# beagle2can.net
KiCad netlist of a schematic drawn in EAGLE
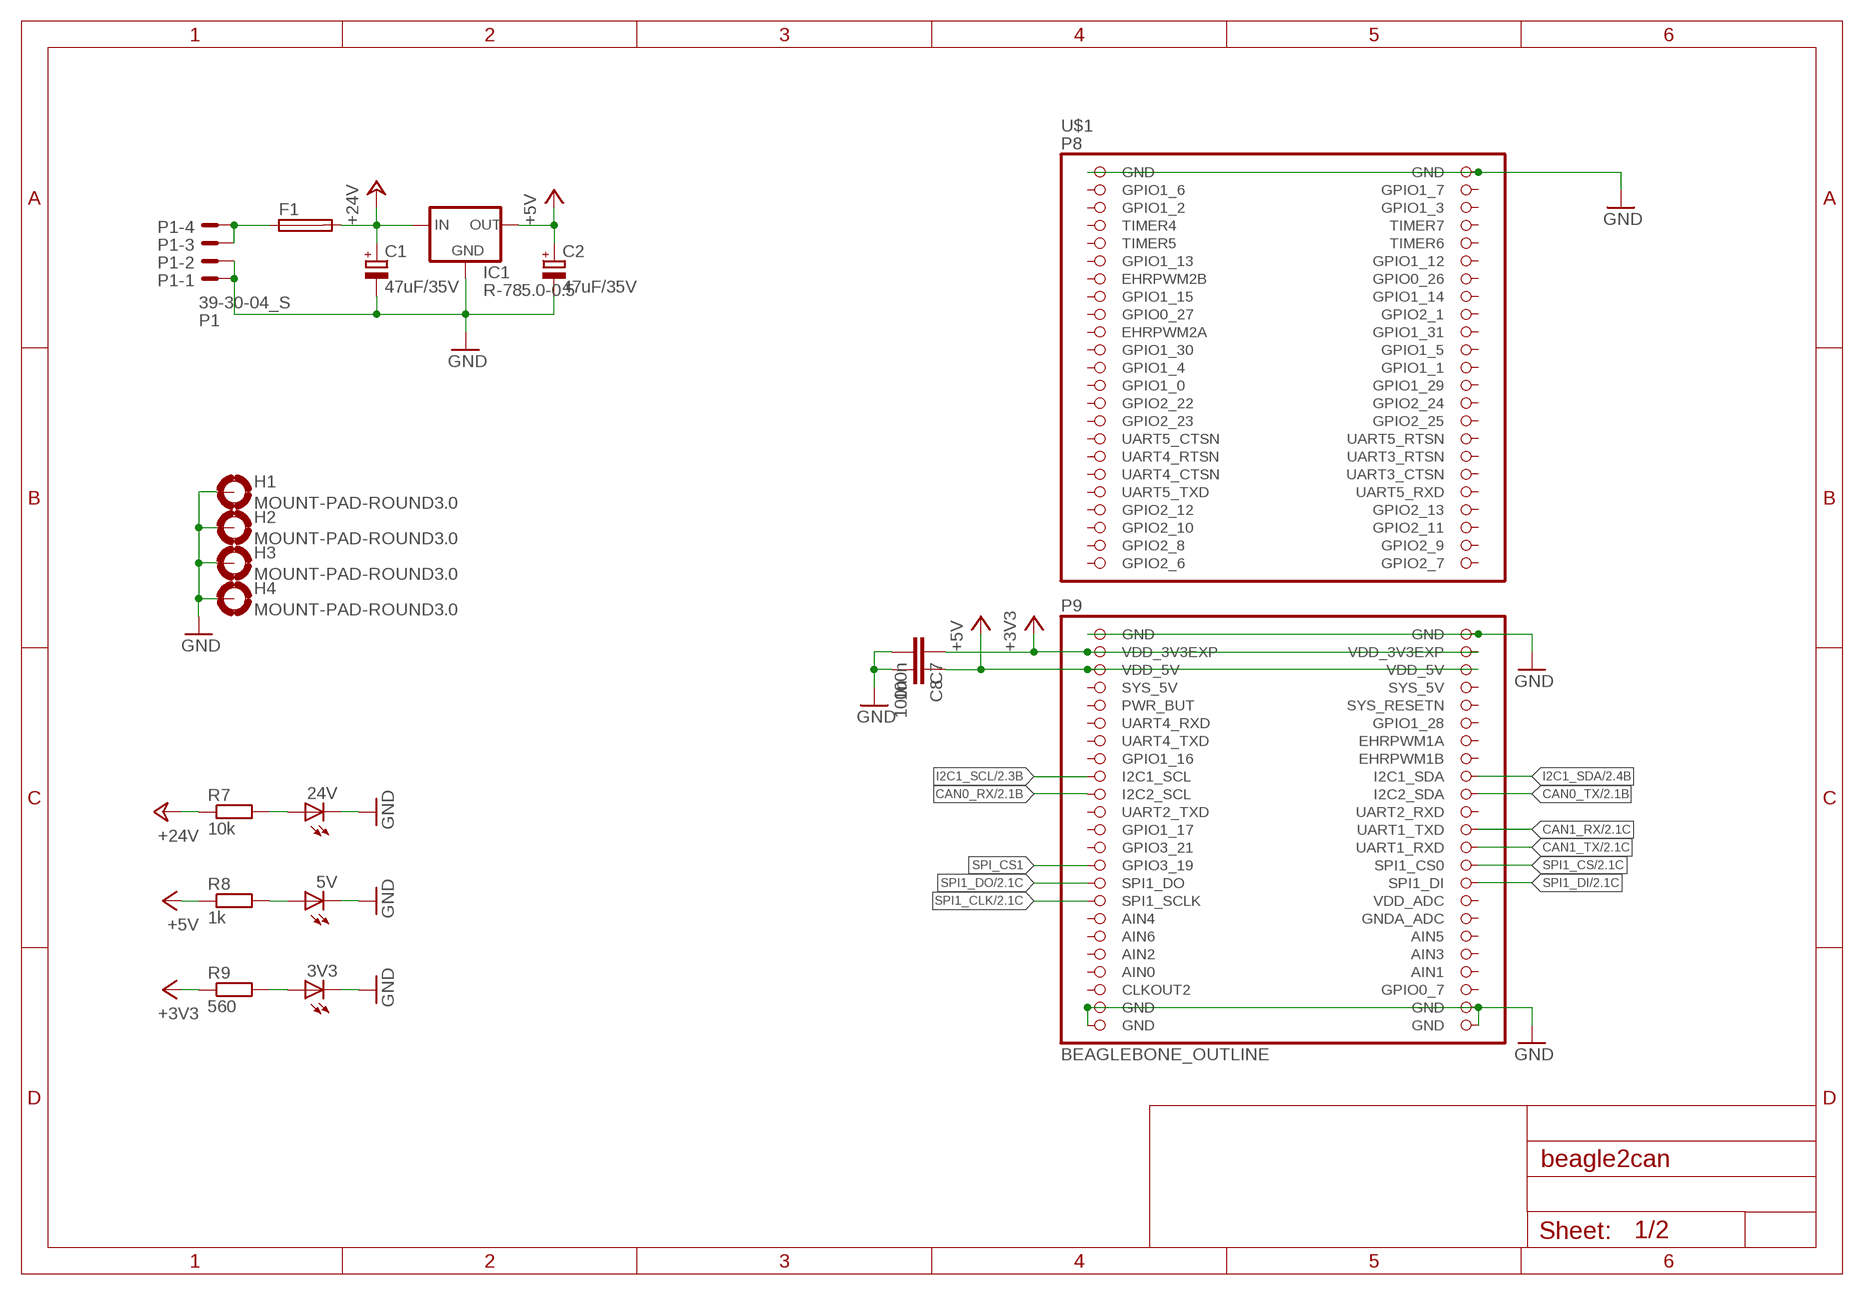
[diagram p0: schematic, sheet 1]
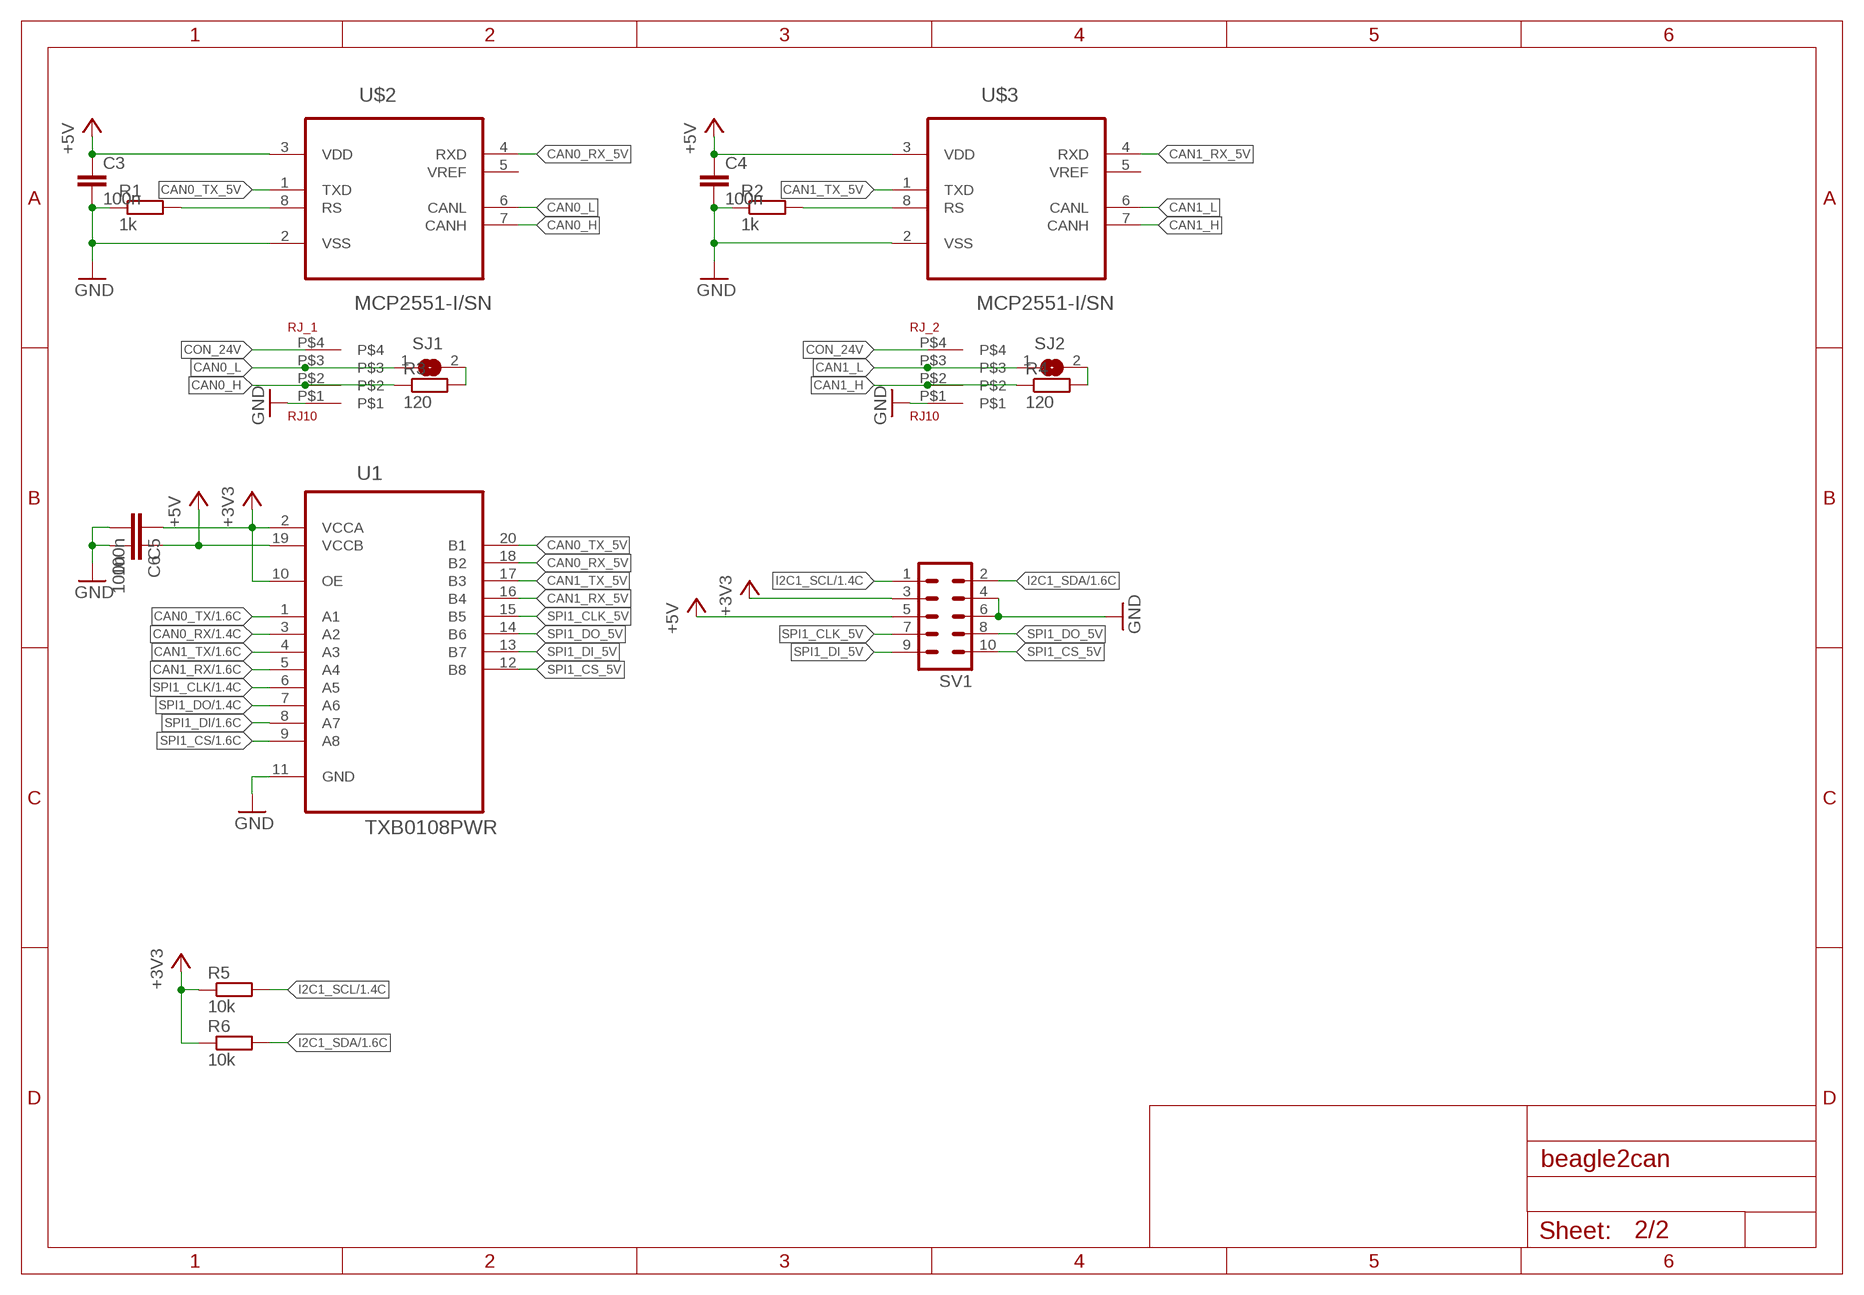
[diagram p1: schematic, sheet 2]

(export (version "E")
  (design (tool "Eeschema 10.0.6"))
  (components
    (comp (ref "3V3")
      (value "LEDCHIP-LED0805")
      (footprint "eagle-import:CHIP-LED0805")
      (libsource (lib "eagle-import") (part "LEDCHIP-LED0805"))
    )
    (comp (ref "5V")
      (value "LEDCHIP-LED0805")
      (footprint "eagle-import:CHIP-LED0805")
      (libsource (lib "eagle-import") (part "LEDCHIP-LED0805"))
    )
    (comp (ref "24V")
      (value "LEDCHIP-LED0805")
      (footprint "eagle-import:CHIP-LED0805")
      (libsource (lib "eagle-import") (part "LEDCHIP-LED0805"))
    )
    (comp (ref "C1")
      (value "47uF/35V")
      (footprint "eagle-import:PANASONIC_D")
      (libsource (lib "eagle-import") (part "CPOL-EUD"))
    )
    (comp (ref "C2")
      (value "47uF/35V")
      (footprint "eagle-import:PANASONIC_D")
      (libsource (lib "eagle-import") (part "CPOL-EUD"))
    )
    (comp (ref "C7")
      (value "100n")
      (footprint "eagle-import:C0603")
      (libsource (lib "eagle-import") (part "C-EUC0603"))
    )
    (comp (ref "C8")
      (value "100n")
      (footprint "eagle-import:C0603")
      (libsource (lib "eagle-import") (part "C-EUC0603"))
    )
    (comp (ref "F1")
      (value "TE5")
      (footprint "eagle-import:TE5")
      (libsource (lib "eagle-import") (part "TE5"))
    )
    (comp (ref "H1")
      (value "MOUNT-PAD-ROUND3.0")
      (footprint "eagle-import:3,0-PAD")
      (libsource (lib "eagle-import") (part "MOUNT-PAD-ROUND3.0"))
    )
    (comp (ref "H2")
      (value "MOUNT-PAD-ROUND3.0")
      (footprint "eagle-import:3,0-PAD")
      (libsource (lib "eagle-import") (part "MOUNT-PAD-ROUND3.0"))
    )
    (comp (ref "H3")
      (value "MOUNT-PAD-ROUND3.0")
      (footprint "eagle-import:3,0-PAD")
      (libsource (lib "eagle-import") (part "MOUNT-PAD-ROUND3.0"))
    )
    (comp (ref "H4")
      (value "MOUNT-PAD-ROUND3.0")
      (footprint "eagle-import:3,0-PAD")
      (libsource (lib "eagle-import") (part "MOUNT-PAD-ROUND3.0"))
    )
    (comp (ref "IC1")
      (value "R-785.0-0.5")
      (footprint "eagle-import:SIP3")
      (fields (field (name "MF") "Recom") (field (name "MPN") "R-785.0-05"))
      (libsource (lib "eagle-import") (part "R-78-0.55.0"))
    )
    (comp (ref "P1")
      (value "39-30-04_S")
      (footprint "eagle-import:39-30-_04_")
      (libsource (lib "eagle-import") (part "39-30-?04?_S"))
    )
    (comp (ref "R7")
      (value "10k")
      (footprint "eagle-import:R0805")
      (libsource (lib "eagle-import") (part "R-EU_R0805"))
    )
    (comp (ref "R8")
      (value "1k")
      (footprint "eagle-import:R0805")
      (libsource (lib "eagle-import") (part "R-EU_R0805"))
    )
    (comp (ref "R9")
      (value "560")
      (footprint "eagle-import:R0805")
      (libsource (lib "eagle-import") (part "R-EU_R0805"))
    )
    (comp (ref "U$1")
      (value "BEAGLEBONE_OUTLINE")
      (footprint "eagle-import:BEAGLEBONE_SHIELD")
      (libsource (lib "eagle-import") (part "BEAGLEBONE_OUTLINE"))
    )
    (comp (ref "C3")
      (value "100n")
      (footprint "eagle-import:C0603")
      (libsource (lib "eagle-import") (part "C-EUC0603"))
    )
    (comp (ref "C4")
      (value "100n")
      (footprint "eagle-import:C0603")
      (libsource (lib "eagle-import") (part "C-EUC0603"))
    )
    (comp (ref "C5")
      (value "100n")
      (footprint "eagle-import:C0603")
      (libsource (lib "eagle-import") (part "C-EUC0603"))
    )
    (comp (ref "C6")
      (value "100n")
      (footprint "eagle-import:C0603")
      (libsource (lib "eagle-import") (part "C-EUC0603"))
    )
    (comp (ref "R1")
      (value "1k")
      (footprint "eagle-import:R0805")
      (libsource (lib "eagle-import") (part "R-EU_R0805"))
    )
    (comp (ref "R2")
      (value "1k")
      (footprint "eagle-import:R0805")
      (libsource (lib "eagle-import") (part "R-EU_R0805"))
    )
    (comp (ref "R3")
      (value "120")
      (footprint "eagle-import:R0805")
      (libsource (lib "eagle-import") (part "R-EU_R0805"))
    )
    (comp (ref "R4")
      (value "120")
      (footprint "eagle-import:R0805")
      (libsource (lib "eagle-import") (part "R-EU_R0805"))
    )
    (comp (ref "R5")
      (value "10k")
      (footprint "eagle-import:R0805")
      (libsource (lib "eagle-import") (part "R-EU_R0805"))
    )
    (comp (ref "R6")
      (value "10k")
      (footprint "eagle-import:R0805")
      (libsource (lib "eagle-import") (part "R-EU_R0805"))
    )
    (comp (ref "RJ_1")
      (value "RJ10")
      (footprint "eagle-import:RJ10")
      (libsource (lib "eagle-import") (part "RJ10"))
    )
    (comp (ref "RJ_2")
      (value "RJ10")
      (footprint "eagle-import:RJ10")
      (libsource (lib "eagle-import") (part "RJ10"))
    )
    (comp (ref "SJ1") (value "SJ") (footprint "eagle-import:SJ") (libsource (lib "eagle-import") (part "SJ")))
    (comp (ref "SJ2") (value "SJ") (footprint "eagle-import:SJ") (libsource (lib "eagle-import") (part "SJ")))
    (comp (ref "SV1")
      (value "ML10L")
      (footprint "eagle-import:ML10L")
      (libsource (lib "eagle-import") (part "ML10L"))
    )
    (comp (ref "U$2")
      (value "MCP2551-I/SN")
      (footprint "eagle-import:SOIC127P600X175-8N")
      (libsource (lib "eagle-import") (part "MCP2551-I/SN"))
    )
    (comp (ref "U$3")
      (value "MCP2551-I/SN")
      (footprint "eagle-import:SOIC127P600X175-8N")
      (libsource (lib "eagle-import") (part "MCP2551-I/SN"))
    )
    (comp (ref "U1")
      (value "TXB0108PWR")
      (footprint "eagle-import:SOP65P640X120-20N")
      (libsource (lib "eagle-import") (part "TXB0108PWR"))
    )
  )
  (nets
    (net (code "1") (name "+3V3") (class "Default")
      (node (ref "C5") (pin "1") (pinfunction "1_1") (pintype "passive"))
      (node (ref "C7") (pin "1") (pinfunction "1_1") (pintype "passive"))
      (node (ref "R5") (pin "1") (pinfunction "1_1") (pintype "passive"))
      (node (ref "R6") (pin "1") (pinfunction "1_1") (pintype "passive"))
      (node (ref "R9") (pin "1") (pinfunction "1_1") (pintype "passive"))
      (node (ref "SV1") (pin "3") (pinfunction "3_3") (pintype "passive"))
      (node (ref "U$1") (pin "49") (pinfunction "VDD_3V3EXP_49") (pintype "power_in"))
      (node (ref "U$1") (pin "50") (pinfunction "VDD_3V3EXP_50") (pintype "power_in"))
      (node (ref "U1") (pin "10") (pinfunction "OE_10") (pintype "input"))
      (node (ref "U1") (pin "2") (pinfunction "VCCA_2") (pintype "power_in"))
    )
    (net (code "2") (name "+5V") (class "Default")
      (node (ref "C2") (pin "+") (pinfunction "+_+") (pintype "passive"))
      (node (ref "C3") (pin "1") (pinfunction "1_1") (pintype "passive"))
      (node (ref "C4") (pin "1") (pinfunction "1_1") (pintype "passive"))
      (node (ref "C6") (pin "1") (pinfunction "1_1") (pintype "passive"))
      (node (ref "C8") (pin "1") (pinfunction "1_1") (pintype "passive"))
      (node (ref "IC1") (pin "3") (pinfunction "OUT_3") (pintype "passive"))
      (node (ref "R8") (pin "1") (pinfunction "1_1") (pintype "passive"))
      (node (ref "SV1") (pin "5") (pinfunction "5_5") (pintype "passive"))
      (node (ref "U$1") (pin "51") (pinfunction "VDD_5V_51") (pintype "power_in"))
      (node (ref "U$1") (pin "52") (pinfunction "VDD_5V_52") (pintype "power_in"))
      (node (ref "U$2") (pin "3") (pinfunction "VDD_3") (pintype "power_in"))
      (node (ref "U$3") (pin "3") (pinfunction "VDD_3") (pintype "power_in"))
      (node (ref "U1") (pin "19") (pinfunction "VCCB_19") (pintype "power_in"))
    )
    (net (code "3") (name "+24V") (class "Default")
      (node (ref "C1") (pin "+") (pinfunction "+_+") (pintype "passive"))
      (node (ref "F1") (pin "2") (pinfunction "2_2") (pintype "passive"))
      (node (ref "IC1") (pin "1") (pinfunction "IN_1") (pintype "input"))
      (node (ref "R7") (pin "1") (pinfunction "1_1") (pintype "passive"))
    )
    (net (code "4") (name "AIN0") (class "Default")
      (node (ref "U$1") (pin "85") (pinfunction "AIN0_85") (pintype "power_in"))
    )
    (net (code "5") (name "CAN0_H") (class "Default")
      (node (ref "R3") (pin "1") (pinfunction "1_1") (pintype "passive"))
      (node (ref "RJ_1") (pin "P$2") (pinfunction "P$2_P$2") (pintype "bidirectional"))
      (node (ref "U$2") (pin "7") (pinfunction "CANH_7") (pintype "bidirectional"))
    )
    (net (code "6") (name "CAN0_L") (class "Default")
      (node (ref "RJ_1") (pin "P$3") (pinfunction "P$3_P$3") (pintype "bidirectional"))
      (node (ref "SJ1") (pin "1") (pinfunction "1_1") (pintype "passive"))
      (node (ref "U$2") (pin "6") (pinfunction "CANL_6") (pintype "bidirectional"))
    )
    (net (code "7") (name "CAN0_RX") (class "Default")
      (node (ref "U$1") (pin "65") (pinfunction "I2C2_SCL_65") (pintype "passive"))
      (node (ref "U1") (pin "3") (pinfunction "A2_3") (pintype "bidirectional"))
    )
    (net (code "8") (name "CAN0_RX_5V") (class "Default")
      (node (ref "U$2") (pin "4") (pinfunction "RXD_4") (pintype "output"))
      (node (ref "U1") (pin "18") (pinfunction "B2_18") (pintype "bidirectional"))
    )
    (net (code "9") (name "CAN0_TX") (class "Default")
      (node (ref "U$1") (pin "66") (pinfunction "I2C2_SDA_66") (pintype "passive"))
      (node (ref "U1") (pin "1") (pinfunction "A1_1") (pintype "bidirectional"))
    )
    (net (code "10") (name "CAN0_TX_5V") (class "Default")
      (node (ref "U$2") (pin "1") (pinfunction "TXD_1") (pintype "input"))
      (node (ref "U1") (pin "20") (pinfunction "B1_20") (pintype "bidirectional"))
    )
    (net (code "11") (name "CAN1_H") (class "Default")
      (node (ref "R4") (pin "1") (pinfunction "1_1") (pintype "passive"))
      (node (ref "RJ_2") (pin "P$2") (pinfunction "P$2_P$2") (pintype "bidirectional"))
      (node (ref "U$3") (pin "7") (pinfunction "CANH_7") (pintype "bidirectional"))
    )
    (net (code "12") (name "CAN1_L") (class "Default")
      (node (ref "RJ_2") (pin "P$3") (pinfunction "P$3_P$3") (pintype "bidirectional"))
      (node (ref "SJ2") (pin "1") (pinfunction "1_1") (pintype "passive"))
      (node (ref "U$3") (pin "6") (pinfunction "CANL_6") (pintype "bidirectional"))
    )
    (net (code "13") (name "CAN1_RX") (class "Default")
      (node (ref "U$1") (pin "70") (pinfunction "UART1_TXD_70") (pintype "passive"))
      (node (ref "U1") (pin "5") (pinfunction "A4_5") (pintype "bidirectional"))
    )
    (net (code "14") (name "CAN1_RX_5V") (class "Default")
      (node (ref "U$3") (pin "4") (pinfunction "RXD_4") (pintype "output"))
      (node (ref "U1") (pin "16") (pinfunction "B4_16") (pintype "bidirectional"))
    )
    (net (code "15") (name "CAN1_TX") (class "Default")
      (node (ref "U$1") (pin "72") (pinfunction "UART1_RXD_72") (pintype "passive"))
      (node (ref "U1") (pin "4") (pinfunction "A3_4") (pintype "bidirectional"))
    )
    (net (code "16") (name "CAN1_TX_5V") (class "Default")
      (node (ref "U$3") (pin "1") (pinfunction "TXD_1") (pintype "input"))
      (node (ref "U1") (pin "17") (pinfunction "B3_17") (pintype "bidirectional"))
    )
    (net (code "17") (name "CON_24V") (class "Default")
      (node (ref "F1") (pin "1") (pinfunction "1_1") (pintype "passive"))
      (node (ref "P1") (pin "3") (pinfunction "P_3") (pintype "passive"))
      (node (ref "P1") (pin "4") (pinfunction "P_4") (pintype "passive"))
      (node (ref "RJ_1") (pin "P$4") (pinfunction "P$4_P$4") (pintype "bidirectional"))
      (node (ref "RJ_2") (pin "P$4") (pinfunction "P$4_P$4") (pintype "bidirectional"))
    )
    (net (code "18") (name "GND") (class "Default")
      (node (ref "24V") (pin "C") (pinfunction "C_C") (pintype "passive"))
      (node (ref "3V3") (pin "C") (pinfunction "C_C") (pintype "passive"))
      (node (ref "5V") (pin "C") (pinfunction "C_C") (pintype "passive"))
      (node (ref "C1") (pin "-") (pinfunction "-_-") (pintype "passive"))
      (node (ref "C2") (pin "-") (pinfunction "-_-") (pintype "passive"))
      (node (ref "C3") (pin "2") (pinfunction "2_2") (pintype "passive"))
      (node (ref "C4") (pin "2") (pinfunction "2_2") (pintype "passive"))
      (node (ref "C5") (pin "2") (pinfunction "2_2") (pintype "passive"))
      (node (ref "C6") (pin "2") (pinfunction "2_2") (pintype "passive"))
      (node (ref "C7") (pin "2") (pinfunction "2_2") (pintype "passive"))
      (node (ref "C8") (pin "2") (pinfunction "2_2") (pintype "passive"))
      (node (ref "H1") (pin "B3,0") (pinfunction "MOUNT_B3,0") (pintype "passive"))
      (node (ref "H2") (pin "B3,0") (pinfunction "MOUNT_B3,0") (pintype "passive"))
      (node (ref "H3") (pin "B3,0") (pinfunction "MOUNT_B3,0") (pintype "passive"))
      (node (ref "H4") (pin "B3,0") (pinfunction "MOUNT_B3,0") (pintype "passive"))
      (node (ref "IC1") (pin "2") (pinfunction "GND_2") (pintype "input"))
      (node (ref "P1") (pin "1") (pinfunction "P_1") (pintype "passive"))
      (node (ref "P1") (pin "2") (pinfunction "P_2") (pintype "passive"))
      (node (ref "R1") (pin "1") (pinfunction "1_1") (pintype "passive"))
      (node (ref "R2") (pin "1") (pinfunction "1_1") (pintype "passive"))
      (node (ref "RJ_1") (pin "P$1") (pinfunction "P$1_P$1") (pintype "bidirectional"))
      (node (ref "RJ_2") (pin "P$1") (pinfunction "P$1_P$1") (pintype "bidirectional"))
      (node (ref "SV1") (pin "4") (pinfunction "4_4") (pintype "passive"))
      (node (ref "SV1") (pin "6") (pinfunction "6_6") (pintype "passive"))
      (node (ref "U$1") (pin "1") (pinfunction "GND_1") (pintype "power_in"))
      (node (ref "U$1") (pin "2") (pinfunction "GND_2") (pintype "power_in"))
      (node (ref "U$1") (pin "47") (pinfunction "GND_47") (pintype "power_in"))
      (node (ref "U$1") (pin "48") (pinfunction "GND_48") (pintype "power_in"))
      (node (ref "U$1") (pin "89") (pinfunction "GND_89") (pintype "power_in"))
      (node (ref "U$1") (pin "90") (pinfunction "GND_90") (pintype "power_in"))
      (node (ref "U$1") (pin "91") (pinfunction "GND_91") (pintype "power_in"))
      (node (ref "U$1") (pin "92") (pinfunction "GND_92") (pintype "power_in"))
      (node (ref "U$2") (pin "2") (pinfunction "VSS_2") (pintype "passive"))
      (node (ref "U$3") (pin "2") (pinfunction "VSS_2") (pintype "passive"))
      (node (ref "U1") (pin "11") (pinfunction "GND_11") (pintype "passive"))
    )
    (net (code "19") (name "I2C1_SCL") (class "Default")
      (node (ref "R5") (pin "2") (pinfunction "2_2") (pintype "passive"))
      (node (ref "SV1") (pin "1") (pinfunction "1_1") (pintype "passive"))
      (node (ref "U$1") (pin "63") (pinfunction "I2C1_SCL_63") (pintype "passive"))
    )
    (net (code "20") (name "I2C1_SDA") (class "Default")
      (node (ref "R6") (pin "2") (pinfunction "2_2") (pintype "passive"))
      (node (ref "SV1") (pin "2") (pinfunction "2_2") (pintype "passive"))
      (node (ref "U$1") (pin "64") (pinfunction "I2C1_SDA_64") (pintype "passive"))
    )
    (net (code "21") (name "Net-(3V3-PadA)") (class "Default")
      (node (ref "3V3") (pin "A") (pinfunction "A_A") (pintype "passive"))
      (node (ref "R9") (pin "2") (pinfunction "2_2") (pintype "passive"))
    )
    (net (code "22") (name "Net-(5V-PadA)") (class "Default")
      (node (ref "5V") (pin "A") (pinfunction "A_A") (pintype "passive"))
      (node (ref "R8") (pin "2") (pinfunction "2_2") (pintype "passive"))
    )
    (net (code "23") (name "Net-(24V-PadA)") (class "Default")
      (node (ref "24V") (pin "A") (pinfunction "A_A") (pintype "passive"))
      (node (ref "R7") (pin "2") (pinfunction "2_2") (pintype "passive"))
    )
    (net (code "24") (name "Net-(R3-Pad2)") (class "Default")
      (node (ref "R3") (pin "2") (pinfunction "2_2") (pintype "passive"))
      (node (ref "SJ1") (pin "2") (pinfunction "2_2") (pintype "passive"))
    )
    (net (code "25") (name "Net-(R4-Pad2)") (class "Default")
      (node (ref "R4") (pin "2") (pinfunction "2_2") (pintype "passive"))
      (node (ref "SJ2") (pin "2") (pinfunction "2_2") (pintype "passive"))
    )
    (net (code "26") (name "Net-(U$2-RS)") (class "Default")
      (node (ref "R1") (pin "2") (pinfunction "2_2") (pintype "passive"))
      (node (ref "U$2") (pin "8") (pinfunction "RS_8") (pintype "input"))
    )
    (net (code "27") (name "Net-(U$3-RS)") (class "Default")
      (node (ref "R2") (pin "2") (pinfunction "2_2") (pintype "passive"))
      (node (ref "U$3") (pin "8") (pinfunction "RS_8") (pintype "input"))
    )
    (net (code "28") (name "SPI1_CLK") (class "Default")
      (node (ref "U$1") (pin "77") (pinfunction "SPI1_SCLK_77") (pintype "passive"))
      (node (ref "U1") (pin "6") (pinfunction "A5_6") (pintype "bidirectional"))
    )
    (net (code "29") (name "SPI1_CLK_5V") (class "Default")
      (node (ref "SV1") (pin "7") (pinfunction "7_7") (pintype "passive"))
      (node (ref "U1") (pin "15") (pinfunction "B5_15") (pintype "bidirectional"))
    )
    (net (code "30") (name "SPI1_CS") (class "Default")
      (node (ref "U$1") (pin "74") (pinfunction "SPI1_CS0_74") (pintype "passive"))
      (node (ref "U1") (pin "9") (pinfunction "A8_9") (pintype "bidirectional"))
    )
    (net (code "31") (name "SPI1_CS_5V") (class "Default")
      (node (ref "SV1") (pin "10") (pinfunction "10_10") (pintype "passive"))
      (node (ref "U1") (pin "12") (pinfunction "B8_12") (pintype "bidirectional"))
    )
    (net (code "32") (name "SPI1_DI") (class "Default")
      (node (ref "U$1") (pin "76") (pinfunction "SPI1_DI_76") (pintype "passive"))
      (node (ref "U1") (pin "8") (pinfunction "A7_8") (pintype "bidirectional"))
    )
    (net (code "33") (name "SPI1_DI_5V") (class "Default")
      (node (ref "SV1") (pin "9") (pinfunction "9_9") (pintype "passive"))
      (node (ref "U1") (pin "13") (pinfunction "B7_13") (pintype "bidirectional"))
    )
    (net (code "34") (name "SPI1_DO") (class "Default")
      (node (ref "U$1") (pin "75") (pinfunction "SPI1_DO_75") (pintype "passive"))
      (node (ref "U1") (pin "7") (pinfunction "A6_7") (pintype "bidirectional"))
    )
    (net (code "35") (name "SPI1_DO_5V") (class "Default")
      (node (ref "SV1") (pin "8") (pinfunction "8_8") (pintype "passive"))
      (node (ref "U1") (pin "14") (pinfunction "B6_14") (pintype "bidirectional"))
    )
    (net (code "36") (name "SPI_CS1") (class "Default")
      (node (ref "U$1") (pin "73") (pinfunction "GPIO3_19_73") (pintype "passive"))
    )
    (net (code "37") (name "SYS_5V") (class "Default")
      (node (ref "U$1") (pin "53") (pinfunction "SYS_5V_53") (pintype "power_in"))
    )
    (net (code "38") (name "unconnected-(U$1-AIN1-Pad86)") (class "Default")
      (node (ref "U$1") (pin "86") (pinfunction "AIN1_86") (pintype "passive"))
    )
    (net (code "39") (name "unconnected-(U$1-AIN2-Pad83)") (class "Default")
      (node (ref "U$1") (pin "83") (pinfunction "AIN2_83") (pintype "passive"))
    )
    (net (code "40") (name "unconnected-(U$1-AIN3-Pad84)") (class "Default")
      (node (ref "U$1") (pin "84") (pinfunction "AIN3_84") (pintype "passive"))
    )
    (net (code "41") (name "unconnected-(U$1-AIN4-Pad79)") (class "Default")
      (node (ref "U$1") (pin "79") (pinfunction "AIN4_79") (pintype "passive"))
    )
    (net (code "42") (name "unconnected-(U$1-AIN5-Pad82)") (class "Default")
      (node (ref "U$1") (pin "82") (pinfunction "AIN5_82") (pintype "passive"))
    )
    (net (code "43") (name "unconnected-(U$1-AIN6-Pad81)") (class "Default")
      (node (ref "U$1") (pin "81") (pinfunction "AIN6_81") (pintype "passive"))
    )
    (net (code "44") (name "unconnected-(U$1-CLKOUT2-Pad87)") (class "Default")
      (node (ref "U$1") (pin "87") (pinfunction "CLKOUT2_87") (pintype "input"))
    )
    (net (code "45") (name "unconnected-(U$1-EHRPWM1A-Pad60)") (class "Default")
      (node (ref "U$1") (pin "60") (pinfunction "EHRPWM1A_60") (pintype "passive"))
    )
    (net (code "46") (name "unconnected-(U$1-EHRPWM1B-Pad62)") (class "Default")
      (node (ref "U$1") (pin "62") (pinfunction "EHRPWM1B_62") (pintype "passive"))
    )
    (net (code "47") (name "unconnected-(U$1-EHRPWM2A-Pad19)") (class "Default")
      (node (ref "U$1") (pin "19") (pinfunction "EHRPWM2A_19") (pintype "passive"))
    )
    (net (code "48") (name "unconnected-(U$1-EHRPWM2B-Pad13)") (class "Default")
      (node (ref "U$1") (pin "13") (pinfunction "EHRPWM2B_13") (pintype "passive"))
    )
    (net (code "49") (name "unconnected-(U$1-GNDA_ADC-Pad80)") (class "Default")
      (node (ref "U$1") (pin "80") (pinfunction "GNDA_ADC_80") (pintype "passive"))
    )
    (net (code "50") (name "unconnected-(U$1-GPIO0_7-Pad88)") (class "Default")
      (node (ref "U$1") (pin "88") (pinfunction "GPIO0_7_88") (pintype "passive"))
    )
    (net (code "51") (name "unconnected-(U$1-GPIO0_26-Pad14)") (class "Default")
      (node (ref "U$1") (pin "14") (pinfunction "GPIO0_26_14") (pintype "passive"))
    )
    (net (code "52") (name "unconnected-(U$1-GPIO0_27-Pad17)") (class "Default")
      (node (ref "U$1") (pin "17") (pinfunction "GPIO0_27_17") (pintype "passive"))
    )
    (net (code "53") (name "unconnected-(U$1-GPIO1_0-Pad25)") (class "Default")
      (node (ref "U$1") (pin "25") (pinfunction "GPIO1_0_25") (pintype "passive"))
    )
    (net (code "54") (name "unconnected-(U$1-GPIO1_1-Pad24)") (class "Default")
      (node (ref "U$1") (pin "24") (pinfunction "GPIO1_1_24") (pintype "passive"))
    )
    (net (code "55") (name "unconnected-(U$1-GPIO1_2-Pad5)") (class "Default")
      (node (ref "U$1") (pin "5") (pinfunction "GPIO1_2_5") (pintype "passive"))
    )
    (net (code "56") (name "unconnected-(U$1-GPIO1_3-Pad6)") (class "Default")
      (node (ref "U$1") (pin "6") (pinfunction "GPIO1_3_6") (pintype "passive"))
    )
    (net (code "57") (name "unconnected-(U$1-GPIO1_4-Pad23)") (class "Default")
      (node (ref "U$1") (pin "23") (pinfunction "GPIO1_4_23") (pintype "passive"))
    )
    (net (code "58") (name "unconnected-(U$1-GPIO1_5-Pad22)") (class "Default")
      (node (ref "U$1") (pin "22") (pinfunction "GPIO1_5_22") (pintype "passive"))
    )
    (net (code "59") (name "unconnected-(U$1-GPIO1_6-Pad3)") (class "Default")
      (node (ref "U$1") (pin "3") (pinfunction "GPIO1_6_3") (pintype "passive"))
    )
    (net (code "60") (name "unconnected-(U$1-GPIO1_7-Pad4)") (class "Default")
      (node (ref "U$1") (pin "4") (pinfunction "GPIO1_7_4") (pintype "passive"))
    )
    (net (code "61") (name "unconnected-(U$1-GPIO1_12-Pad12)") (class "Default")
      (node (ref "U$1") (pin "12") (pinfunction "GPIO1_12_12") (pintype "passive"))
    )
    (net (code "62") (name "unconnected-(U$1-GPIO1_13-Pad11)") (class "Default")
      (node (ref "U$1") (pin "11") (pinfunction "GPIO1_13_11") (pintype "passive"))
    )
    (net (code "63") (name "unconnected-(U$1-GPIO1_14-Pad16)") (class "Default")
      (node (ref "U$1") (pin "16") (pinfunction "GPIO1_14_16") (pintype "passive"))
    )
    (net (code "64") (name "unconnected-(U$1-GPIO1_15-Pad15)") (class "Default")
      (node (ref "U$1") (pin "15") (pinfunction "GPIO1_15_15") (pintype "passive"))
    )
    (net (code "65") (name "unconnected-(U$1-GPIO1_16-Pad61)") (class "Default")
      (node (ref "U$1") (pin "61") (pinfunction "GPIO1_16_61") (pintype "passive"))
    )
    (net (code "66") (name "unconnected-(U$1-GPIO1_17-Pad69)") (class "Default")
      (node (ref "U$1") (pin "69") (pinfunction "GPIO1_17_69") (pintype "passive"))
    )
    (net (code "67") (name "unconnected-(U$1-GPIO1_28-Pad58)") (class "Default")
      (node (ref "U$1") (pin "58") (pinfunction "GPIO1_28_58") (pintype "passive"))
    )
    (net (code "68") (name "unconnected-(U$1-GPIO1_29-Pad26)") (class "Default")
      (node (ref "U$1") (pin "26") (pinfunction "GPIO1_29_26") (pintype "passive"))
    )
    (net (code "69") (name "unconnected-(U$1-GPIO1_30-Pad21)") (class "Default")
      (node (ref "U$1") (pin "21") (pinfunction "GPIO1_30_21") (pintype "passive"))
    )
    (net (code "70") (name "unconnected-(U$1-GPIO1_31-Pad20)") (class "Default")
      (node (ref "U$1") (pin "20") (pinfunction "GPIO1_31_20") (pintype "passive"))
    )
    (net (code "71") (name "unconnected-(U$1-GPIO2_1-Pad18)") (class "Default")
      (node (ref "U$1") (pin "18") (pinfunction "GPIO2_1_18") (pintype "passive"))
    )
    (net (code "72") (name "unconnected-(U$1-GPIO2_6-Pad45)") (class "Default")
      (node (ref "U$1") (pin "45") (pinfunction "GPIO2_6_45") (pintype "passive"))
    )
    (net (code "73") (name "unconnected-(U$1-GPIO2_7-Pad46)") (class "Default")
      (node (ref "U$1") (pin "46") (pinfunction "GPIO2_7_46") (pintype "passive"))
    )
    (net (code "74") (name "unconnected-(U$1-GPIO2_8-Pad43)") (class "Default")
      (node (ref "U$1") (pin "43") (pinfunction "GPIO2_8_43") (pintype "passive"))
    )
    (net (code "75") (name "unconnected-(U$1-GPIO2_9-Pad44)") (class "Default")
      (node (ref "U$1") (pin "44") (pinfunction "GPIO2_9_44") (pintype "passive"))
    )
    (net (code "76") (name "unconnected-(U$1-GPIO2_10-Pad41)") (class "Default")
      (node (ref "U$1") (pin "41") (pinfunction "GPIO2_10_41") (pintype "passive"))
    )
    (net (code "77") (name "unconnected-(U$1-GPIO2_11-Pad42)") (class "Default")
      (node (ref "U$1") (pin "42") (pinfunction "GPIO2_11_42") (pintype "passive"))
    )
    (net (code "78") (name "unconnected-(U$1-GPIO2_12-Pad39)") (class "Default")
      (node (ref "U$1") (pin "39") (pinfunction "GPIO2_12_39") (pintype "passive"))
    )
    (net (code "79") (name "unconnected-(U$1-GPIO2_13-Pad40)") (class "Default")
      (node (ref "U$1") (pin "40") (pinfunction "GPIO2_13_40") (pintype "passive"))
    )
    (net (code "80") (name "unconnected-(U$1-GPIO2_22-Pad27)") (class "Default")
      (node (ref "U$1") (pin "27") (pinfunction "GPIO2_22_27") (pintype "passive"))
    )
    (net (code "81") (name "unconnected-(U$1-GPIO2_23-Pad29)") (class "Default")
      (node (ref "U$1") (pin "29") (pinfunction "GPIO2_23_29") (pintype "passive"))
    )
    (net (code "82") (name "unconnected-(U$1-GPIO2_24-Pad28)") (class "Default")
      (node (ref "U$1") (pin "28") (pinfunction "GPIO2_24_28") (pintype "passive"))
    )
    (net (code "83") (name "unconnected-(U$1-GPIO2_25-Pad30)") (class "Default")
      (node (ref "U$1") (pin "30") (pinfunction "GPIO2_25_30") (pintype "passive"))
    )
    (net (code "84") (name "unconnected-(U$1-GPIO3_21-Pad71)") (class "Default")
      (node (ref "U$1") (pin "71") (pinfunction "GPIO3_21_71") (pintype "passive"))
    )
    (net (code "85") (name "unconnected-(U$1-PWR_BUT-Pad55)") (class "Default")
      (node (ref "U$1") (pin "55") (pinfunction "PWR_BUT_55") (pintype "passive"))
    )
    (net (code "86") (name "unconnected-(U$1-SYS_5V-Pad54)") (class "Default")
      (node (ref "U$1") (pin "54") (pinfunction "SYS_5V_54") (pintype "passive"))
    )
    (net (code "87") (name "unconnected-(U$1-SYS_RESETN-Pad56)") (class "Default")
      (node (ref "U$1") (pin "56") (pinfunction "SYS_RESETN_56") (pintype "passive"))
    )
    (net (code "88") (name "unconnected-(U$1-TIMER4-Pad7)") (class "Default")
      (node (ref "U$1") (pin "7") (pinfunction "TIMER4_7") (pintype "passive"))
    )
    (net (code "89") (name "unconnected-(U$1-TIMER5-Pad9)") (class "Default")
      (node (ref "U$1") (pin "9") (pinfunction "TIMER5_9") (pintype "passive"))
    )
    (net (code "90") (name "unconnected-(U$1-TIMER6-Pad10)") (class "Default")
      (node (ref "U$1") (pin "10") (pinfunction "TIMER6_10") (pintype "passive"))
    )
    (net (code "91") (name "unconnected-(U$1-TIMER7-Pad8)") (class "Default")
      (node (ref "U$1") (pin "8") (pinfunction "TIMER7_8") (pintype "passive"))
    )
    (net (code "92") (name "unconnected-(U$1-UART2_RXD-Pad68)") (class "Default")
      (node (ref "U$1") (pin "68") (pinfunction "UART2_RXD_68") (pintype "passive"))
    )
    (net (code "93") (name "unconnected-(U$1-UART2_TXD-Pad67)") (class "Default")
      (node (ref "U$1") (pin "67") (pinfunction "UART2_TXD_67") (pintype "passive"))
    )
    (net (code "94") (name "unconnected-(U$1-UART3_CTSN-Pad36)") (class "Default")
      (node (ref "U$1") (pin "36") (pinfunction "UART3_CTSN_36") (pintype "passive"))
    )
    (net (code "95") (name "unconnected-(U$1-UART3_RTSN-Pad34)") (class "Default")
      (node (ref "U$1") (pin "34") (pinfunction "UART3_RTSN_34") (pintype "passive"))
    )
    (net (code "96") (name "unconnected-(U$1-UART4_CTSN-Pad35)") (class "Default")
      (node (ref "U$1") (pin "35") (pinfunction "UART4_CTSN_35") (pintype "passive"))
    )
    (net (code "97") (name "unconnected-(U$1-UART4_RTSN-Pad33)") (class "Default")
      (node (ref "U$1") (pin "33") (pinfunction "UART4_RTSN_33") (pintype "passive"))
    )
    (net (code "98") (name "unconnected-(U$1-UART4_RXD-Pad57)") (class "Default")
      (node (ref "U$1") (pin "57") (pinfunction "UART4_RXD_57") (pintype "passive"))
    )
    (net (code "99") (name "unconnected-(U$1-UART4_TXD-Pad59)") (class "Default")
      (node (ref "U$1") (pin "59") (pinfunction "UART4_TXD_59") (pintype "passive"))
    )
    (net (code "100") (name "unconnected-(U$1-UART5_CTSN-Pad31)") (class "Default")
      (node (ref "U$1") (pin "31") (pinfunction "UART5_CTSN_31") (pintype "passive"))
    )
    (net (code "101") (name "unconnected-(U$1-UART5_RTSN-Pad32)") (class "Default")
      (node (ref "U$1") (pin "32") (pinfunction "UART5_RTSN_32") (pintype "passive"))
    )
    (net (code "102") (name "unconnected-(U$1-UART5_RXD-Pad38)") (class "Default")
      (node (ref "U$1") (pin "38") (pinfunction "UART5_RXD_38") (pintype "passive"))
    )
    (net (code "103") (name "unconnected-(U$1-UART5_TXD-Pad37)") (class "Default")
      (node (ref "U$1") (pin "37") (pinfunction "UART5_TXD_37") (pintype "passive"))
    )
    (net (code "104") (name "unconnected-(U$1-VDD_ADC-Pad78)") (class "Default")
      (node (ref "U$1") (pin "78") (pinfunction "VDD_ADC_78") (pintype "passive"))
    )
    (net (code "105") (name "unconnected-(U$2-VREF-Pad5)") (class "Default")
      (node (ref "U$2") (pin "5") (pinfunction "VREF_5") (pintype "output"))
    )
    (net (code "106") (name "unconnected-(U$3-VREF-Pad5)") (class "Default")
      (node (ref "U$3") (pin "5") (pinfunction "VREF_5") (pintype "output"))
    )
  )
)
